# rx_path_lp_filter.net
KiCad netlist of a schematic drawn in Altium Designer
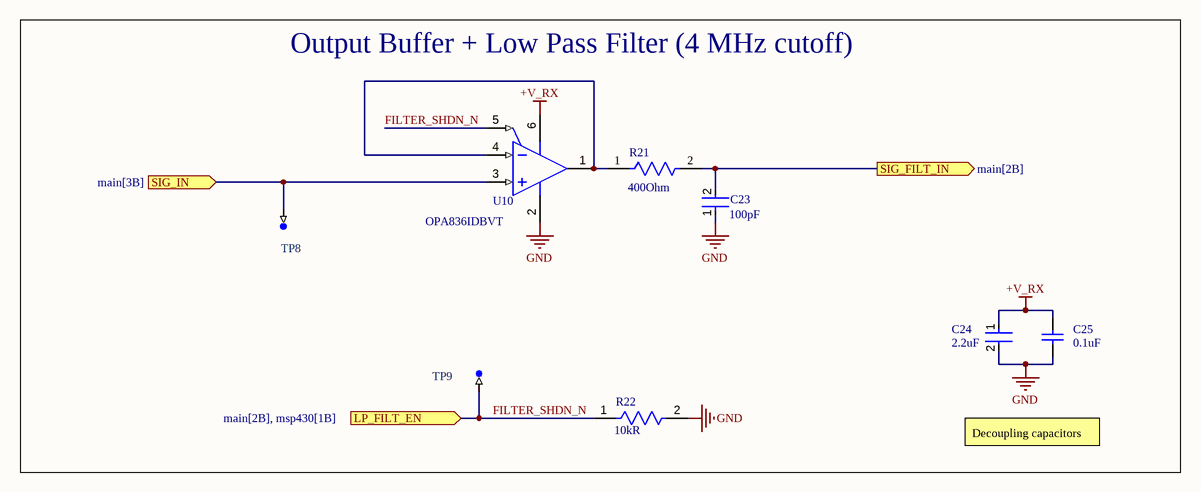
[diagram p0: rx_path_lp_filter.SchDoc]

(export (version "E")
  (design (tool "Eeschema 10.0.6"))
  (components
    (comp (ref "C23")
      (value "04025A101FAT2A")
      (footprint "FP-0402-L_1_0_1-W_0_5_0_1-MFG")
      (fields
        (field (name "CAPACITANCE") "100pF")
        (field (name "VOLTAGE") "50V")
        (field (name "TOLERANCE") "1%")
      )
      (libsource (lib "Altium Content Vault") (part "b4654b650e69147ec39a6b967a45e02"))
    )
    (comp (ref "C24")
      (value "C1005X7S1A225K050BC")
      (footprint "FP-C1005-050-0_15-0_1-MFG")
      (fields (field (name "CAPACITANCE") "2.2uF") (field (name "TOLERANCE") "10%"))
      (libsource (lib "Altium Content Vault") (part "b4654b650e69147ec39a6b967a45e02"))
    )
    (comp (ref "C25")
      (value "C0402C104K4RACTU")
      (footprint "CAPC1005X55X30LL05T10")
      (fields (field (name "MANUFACTURER") "Kemet") (field (name "CAPACITANCE") "0.1uF"))
      (libsource (lib "Altium Content Vault") (part "CAP"))
    )
    (comp (ref "R21")
      (value "CRCW0402402RFKEDC")
      (footprint "FP-CRCW0402-C-e3-MFG")
      (fields (field (name "RESISTANCE") "400Ohm") (field (name "TOLERANCE") "1%"))
      (libsource (lib "Altium Content Vault") (part "1029c3af85768c4190bb7ad29bc67b5"))
    )
    (comp (ref "R22")
      (value "CRCW040210K0JNED")
      (footprint "FP-CRCW0402-e3-IPC_B")
      (fields (field (name "RESISTANCE") "10kR") (field (name "TOLERANCE") "5%"))
      (libsource (lib "Altium Content Vault") (part "1029c3af85768c4190bb7ad29bc67b5"))
    )
    (comp (ref "TP8")
      (value "TP-SM-C-100")
      (footprint "TP-SM-C-100")
      (description "Test Point, Surface Mount, Circular, Pad Diameter 1 mm")
      (libsource (lib "wulpus") (part "CMP-0484-00002-1"))
    )
    (comp (ref "TP9")
      (value "TP-SM-C-100")
      (footprint "TP-SM-C-100")
      (description "Test Point, Surface Mount, Circular, Pad Diameter 1 mm")
      (libsource (lib "wulpus") (part "CMP-0484-00002-1"))
    )
    (comp (ref "U10")
      (value "OPA836IDBVT")
      (footprint "DBV0006A_L")
      (fields (field (name "MANUFACTURER") "Texas Instruments"))
      (libsource (lib "wulpus") (part "CMP-0018-00480-2"))
    )
  )
  (nets
    (net (code "1") (name "+V_RX") (class "Default")
      (node (ref "C24") (pin "1") (pinfunction "1_1") (pintype "passive"))
      (node (ref "C25") (pin "2") (pinfunction "2_2") (pintype "passive"))
      (node (ref "U10") (pin "6") (pinfunction "VS+_6") (pintype "power_in"))
    )
    (net (code "2") (name "/FILTER_SHDN_N") (class "Default")
      (node (ref "R22") (pin "1") (pinfunction "1_1") (pintype "passive"))
      (node (ref "TP9") (pin "1") (pinfunction "1_1") (pintype "input"))
      (node (ref "U10") (pin "5") (pinfunction "~{PD}_5") (pintype "input"))
    )
    (net (code "3") (name "/SIG_FILT_IN") (class "Default")
      (node (ref "C23") (pin "2") (pinfunction "2_2") (pintype "passive"))
      (node (ref "R21") (pin "2") (pinfunction "2_2") (pintype "passive"))
    )
    (net (code "4") (name "/SIG_IN") (class "Default")
      (node (ref "TP8") (pin "1") (pinfunction "1_1") (pintype "input"))
      (node (ref "U10") (pin "3") (pinfunction "VIN+_3") (pintype "input"))
    )
    (net (code "5") (name "GND") (class "Default")
      (node (ref "C23") (pin "1") (pinfunction "1_1") (pintype "passive"))
      (node (ref "C24") (pin "2") (pinfunction "2_2") (pintype "passive"))
      (node (ref "C25") (pin "1") (pinfunction "1_1") (pintype "passive"))
      (node (ref "R22") (pin "2") (pinfunction "2_2") (pintype "passive"))
      (node (ref "U10") (pin "2") (pinfunction "VS-_2") (pintype "power_in"))
    )
    (net (code "6") (name "Net-(U10-VIN-)") (class "Default")
      (node (ref "R21") (pin "1") (pinfunction "1_1") (pintype "passive"))
      (node (ref "U10") (pin "1") (pinfunction "VOUT_1") (pintype "tri_state"))
      (node (ref "U10") (pin "4") (pinfunction "VIN-_4") (pintype "input"))
    )
  )
)
